# DenScript_Tactile_Switch_V1_0.net
KiCad netlist of a schematic drawn in EAGLE
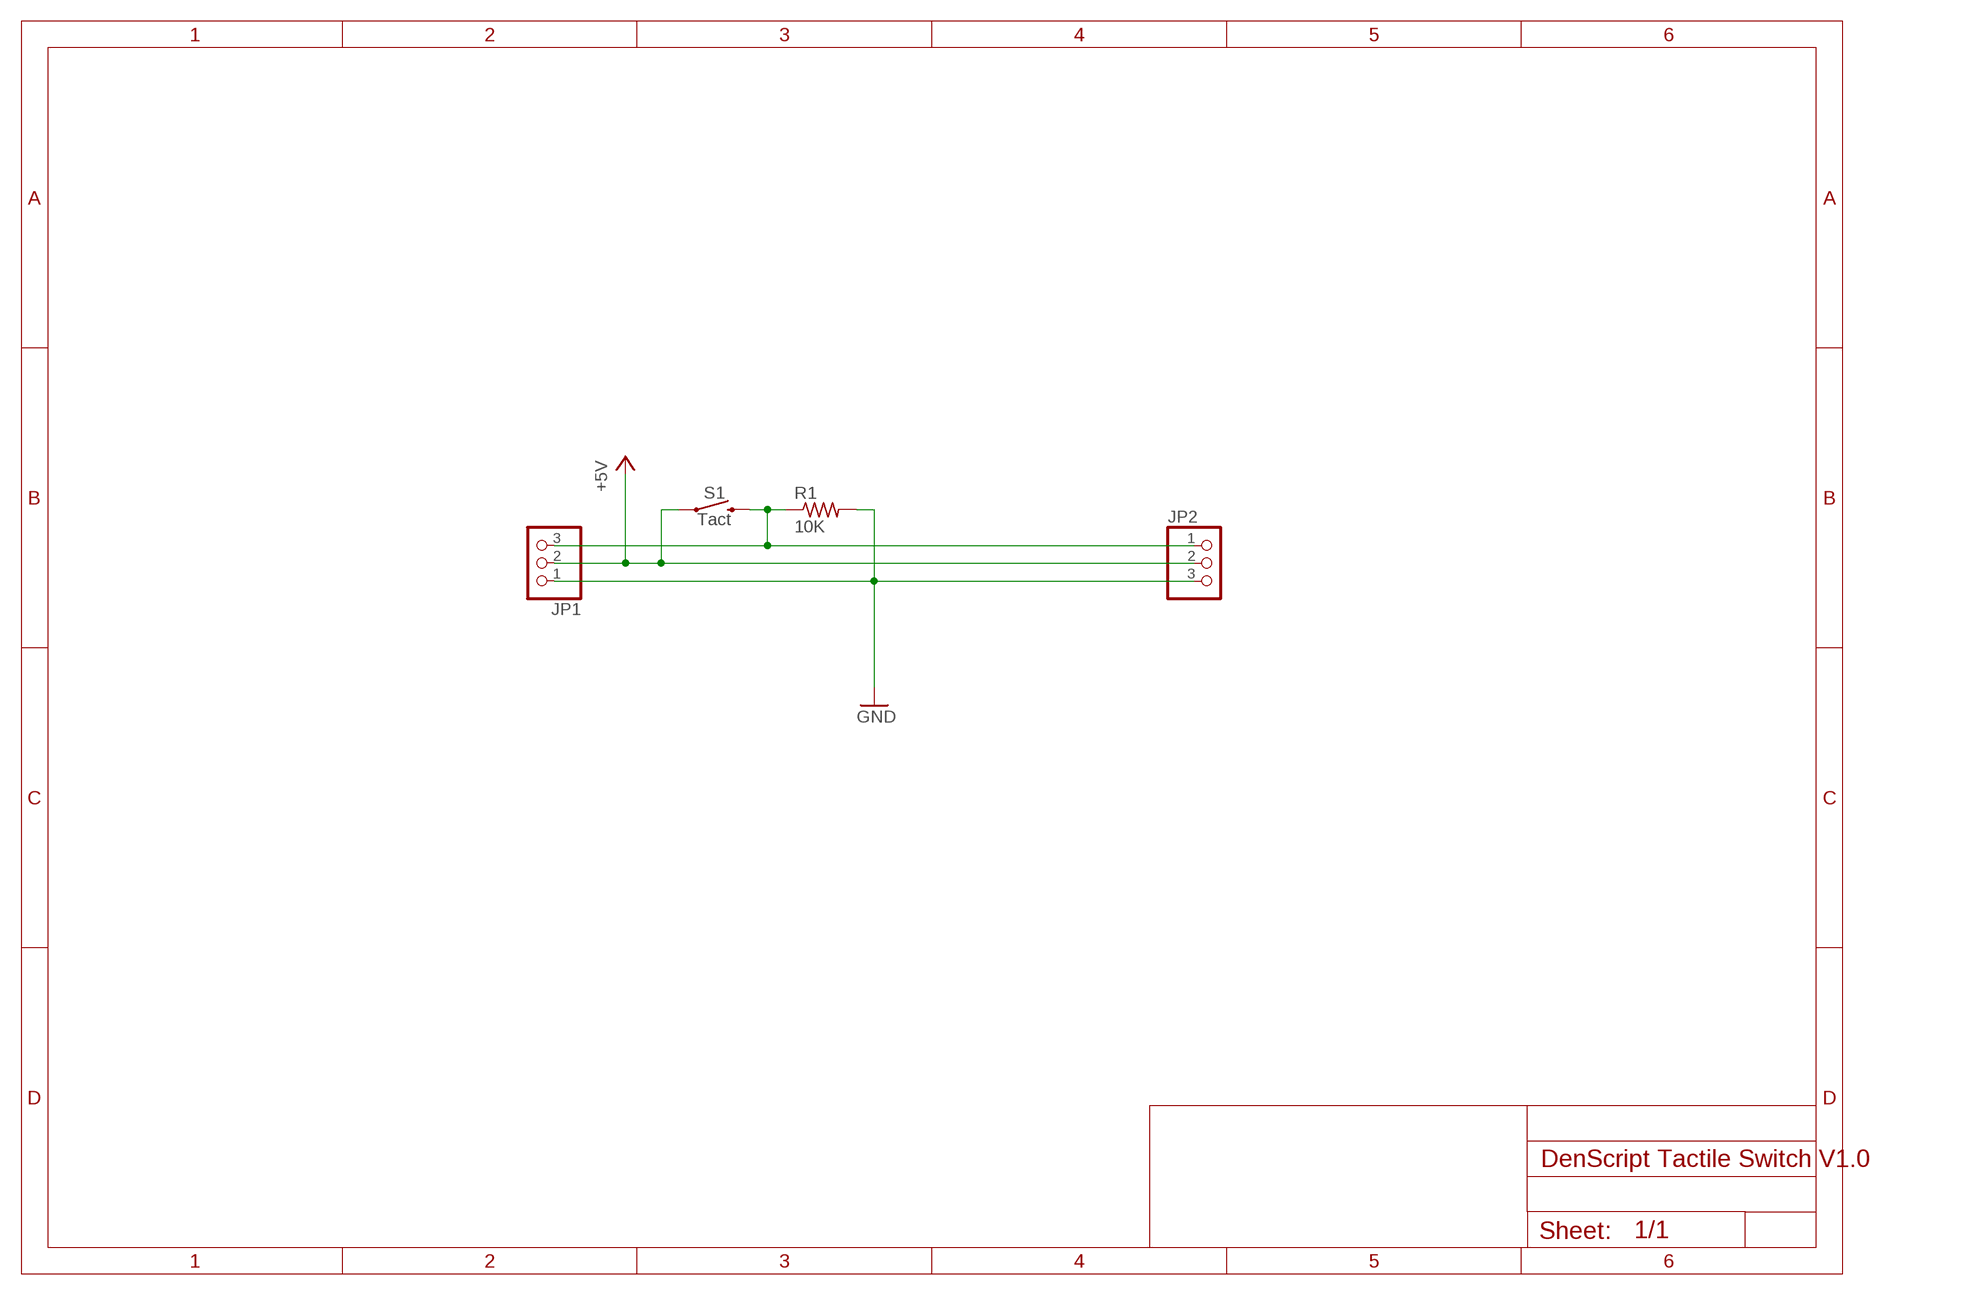
[diagram p0: schematic, sheet 1]

(export (version "E")
  (design (tool "Eeschema 10.0.6"))
  (components
    (comp (ref "JP1")
      (value "PINHD-1X3")
      (footprint "eagle-import:1X03")
      (libsource (lib "eagle-import") (part "PINHD-1X3"))
    )
    (comp (ref "JP2")
      (value "PINHD-1X3")
      (footprint "eagle-import:1X03")
      (libsource (lib "eagle-import") (part "PINHD-1X3"))
    )
    (comp (ref "R1")
      (value "10K")
      (footprint "eagle-import:R0603")
      (libsource (lib "eagle-import") (part "R-US_R0603"))
    )
    (comp (ref "S1")
      (value "Tact")
      (footprint "eagle-import:TACTILE_SWITCH_PTH_6.0MM")
      (libsource (lib "eagle-import") (part "MOMENTARY-SWITCH-SPST-PTH-6.0MM"))
    )
  )
  (nets
    (net (code "1") (name "+5V") (class "Default")
      (node (ref "JP1") (pin "2") (pinfunction "2_2") (pintype "passive"))
      (node (ref "JP2") (pin "2") (pinfunction "2_2") (pintype "passive"))
      (node (ref "S1") (pin "1") (pinfunction "1_1") (pintype "passive"))
    )
    (net (code "2") (name "GND") (class "Default")
      (node (ref "JP1") (pin "1") (pinfunction "1_1") (pintype "passive"))
      (node (ref "JP2") (pin "3") (pinfunction "3_3") (pintype "passive"))
      (node (ref "R1") (pin "2") (pinfunction "2_2") (pintype "passive"))
    )
    (net (code "3") (name "Net-(S1-2)") (class "Default")
      (node (ref "JP1") (pin "3") (pinfunction "3_3") (pintype "passive"))
      (node (ref "JP2") (pin "1") (pinfunction "1_1") (pintype "passive"))
      (node (ref "R1") (pin "1") (pinfunction "1_1") (pintype "passive"))
      (node (ref "S1") (pin "3") (pinfunction "2_3") (pintype "passive"))
    )
  )
)
